# Pulsar_Buddy.net
KiCad netlist of a schematic drawn in EAGLE
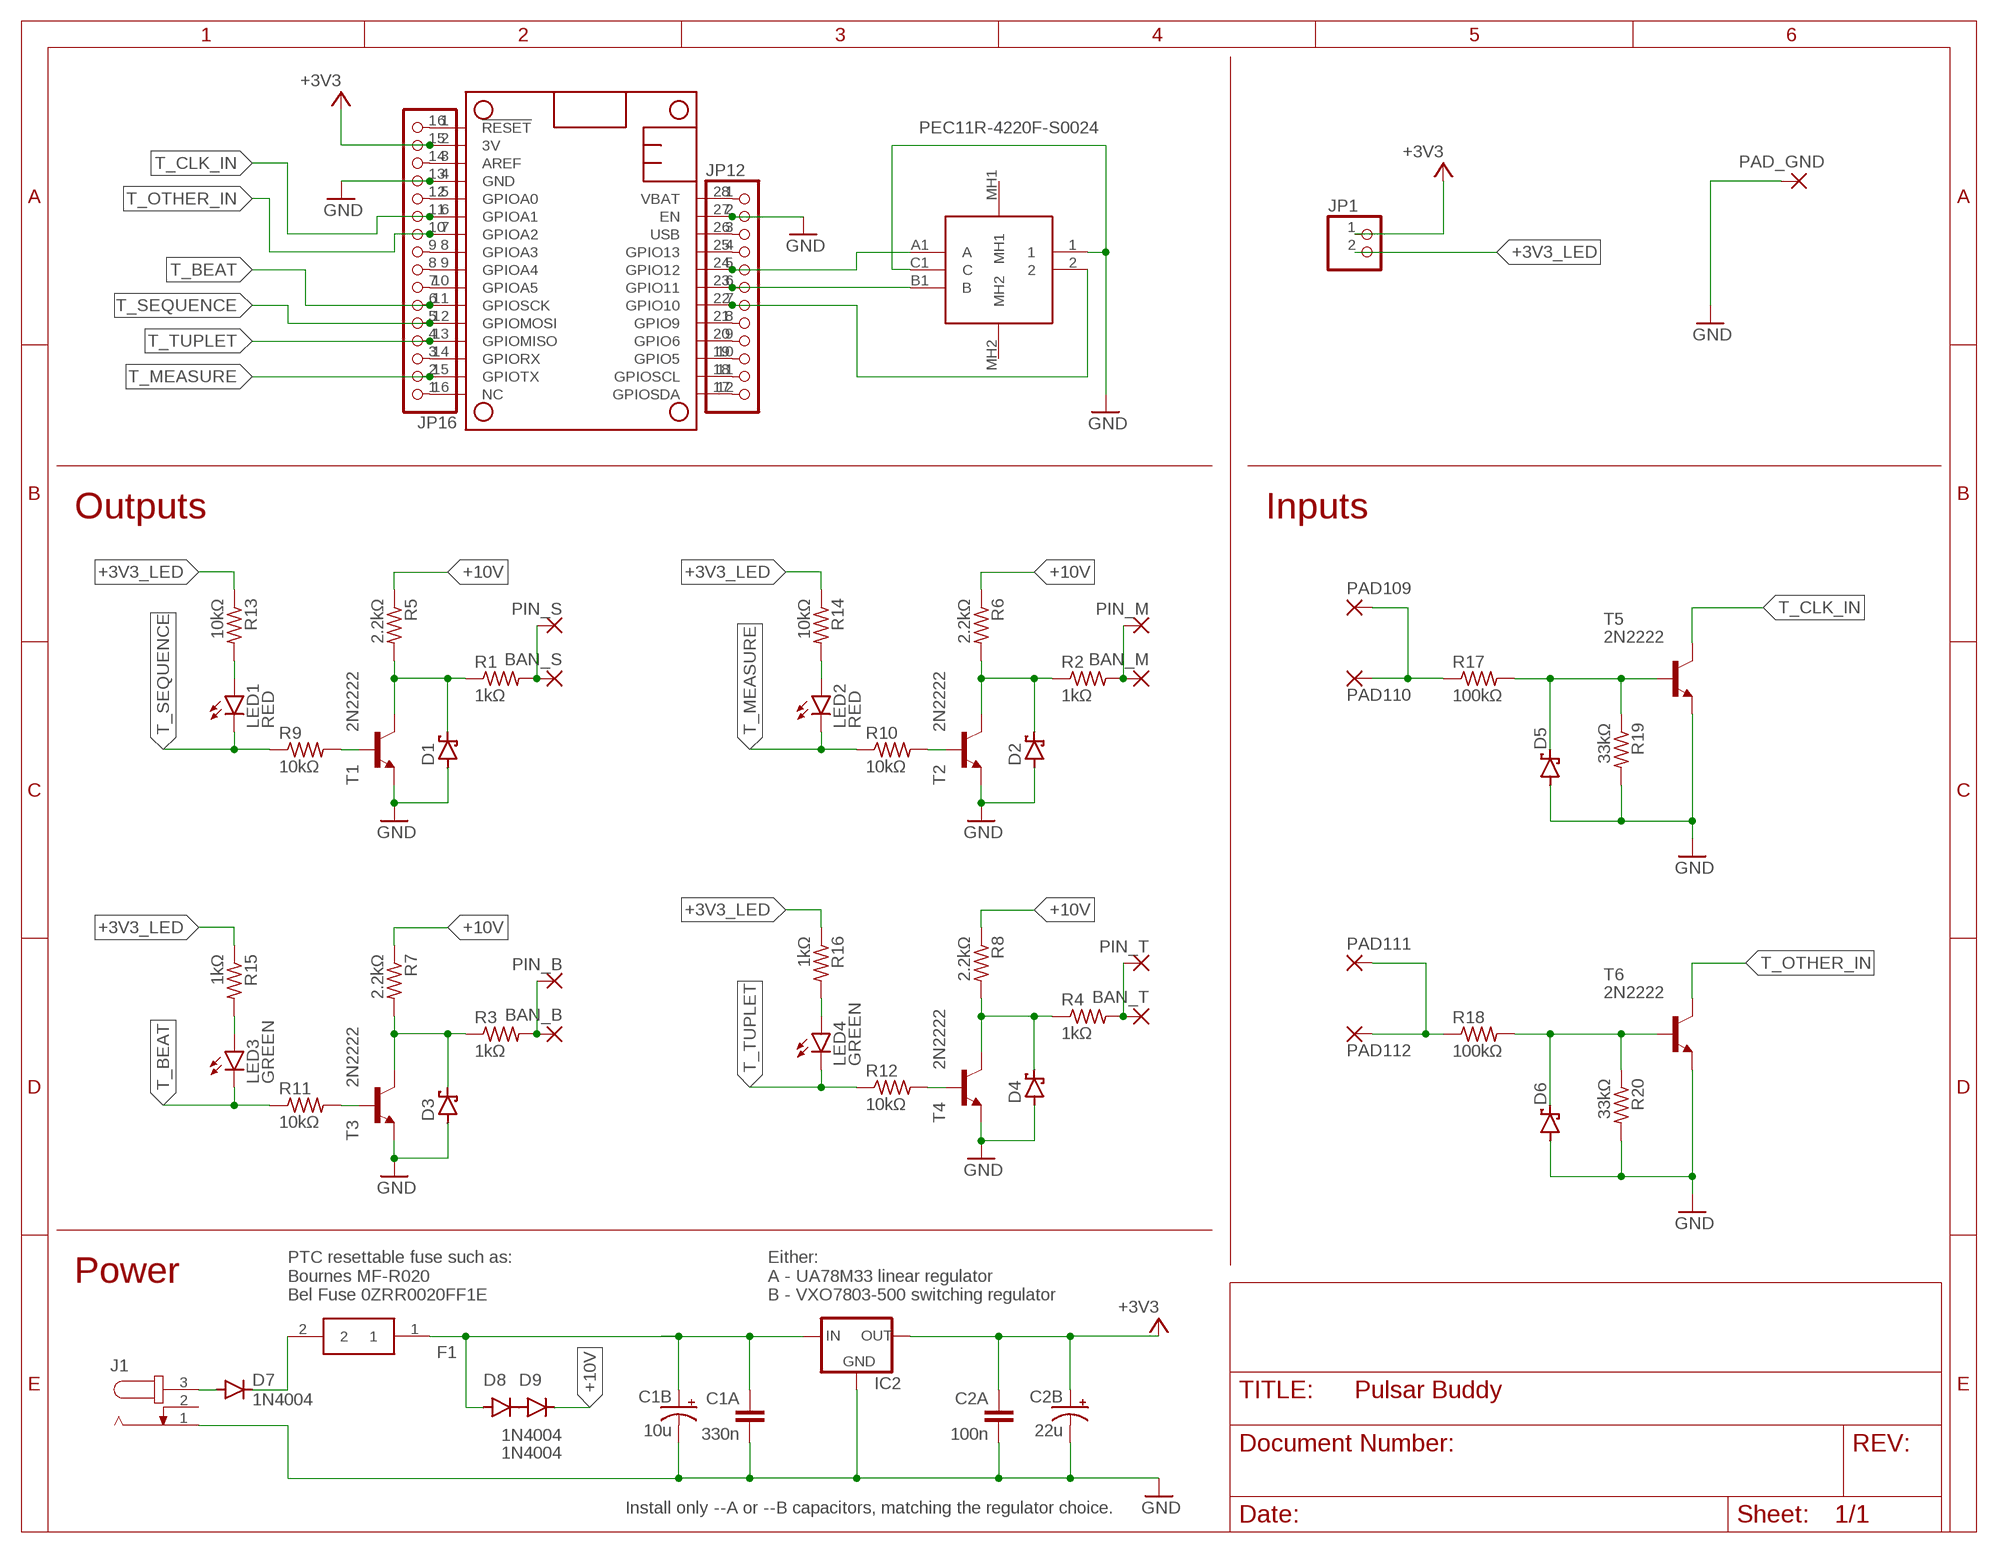
[diagram p0: schematic, sheet 1]

(export (version "E")
  (design (tool "Eeschema 10.0.6"))
  (components
    (comp (ref "BAN_B")
      (value "WIREPADBANANA")
      (footprint "eagle-import:BANANA")
      (libsource (lib "eagle-import") (part "WIREPADBANANA"))
    )
    (comp (ref "BAN_M")
      (value "WIREPADBANANA")
      (footprint "eagle-import:BANANA")
      (libsource (lib "eagle-import") (part "WIREPADBANANA"))
    )
    (comp (ref "BAN_S")
      (value "WIREPADBANANA")
      (footprint "eagle-import:BANANA")
      (libsource (lib "eagle-import") (part "WIREPADBANANA"))
    )
    (comp (ref "BAN_T")
      (value "WIREPADBANANA")
      (footprint "eagle-import:BANANA")
      (libsource (lib "eagle-import") (part "WIREPADBANANA"))
    )
    (comp (ref "C1A")
      (value "330n")
      (footprint "eagle-import:C025-024X044")
      (libsource (lib "eagle-import") (part "C-EU025-024X044"))
    )
    (comp (ref "C1B")
      (value "10u")
      (footprint "eagle-import:E5-5")
      (libsource (lib "eagle-import") (part "CPOL-USE5-5"))
    )
    (comp (ref "C2A")
      (value "100n")
      (footprint "eagle-import:C025-024X044")
      (libsource (lib "eagle-import") (part "C-EU025-024X044"))
    )
    (comp (ref "C2B")
      (value "22u")
      (footprint "eagle-import:E5-5")
      (libsource (lib "eagle-import") (part "CPOL-USE5-5"))
    )
    (comp (ref "D1")
      (value "SCHOTTKY-DIODEDO35-7")
      (footprint "eagle-import:DO35-7")
      (libsource (lib "eagle-import") (part "SCHOTTKY-DIODEDO35-7"))
    )
    (comp (ref "D2")
      (value "SCHOTTKY-DIODEDO35-7")
      (footprint "eagle-import:DO35-7")
      (libsource (lib "eagle-import") (part "SCHOTTKY-DIODEDO35-7"))
    )
    (comp (ref "D3")
      (value "SCHOTTKY-DIODEDO35-7")
      (footprint "eagle-import:DO35-7")
      (libsource (lib "eagle-import") (part "SCHOTTKY-DIODEDO35-7"))
    )
    (comp (ref "D4")
      (value "SCHOTTKY-DIODEDO35-7")
      (footprint "eagle-import:DO35-7")
      (libsource (lib "eagle-import") (part "SCHOTTKY-DIODEDO35-7"))
    )
    (comp (ref "D5")
      (value "SCHOTTKY-DIODEDO35-7")
      (footprint "eagle-import:DO35-7")
      (libsource (lib "eagle-import") (part "SCHOTTKY-DIODEDO35-7"))
    )
    (comp (ref "D6")
      (value "SCHOTTKY-DIODEDO35-7")
      (footprint "eagle-import:DO35-7")
      (libsource (lib "eagle-import") (part "SCHOTTKY-DIODEDO35-7"))
    )
    (comp (ref "D7")
      (value "1N4004")
      (footprint "eagle-import:DO41-10")
      (libsource (lib "eagle-import") (part "1N4004"))
    )
    (comp (ref "D8")
      (value "1N4004")
      (footprint "eagle-import:DO41-10")
      (libsource (lib "eagle-import") (part "1N4004"))
    )
    (comp (ref "D9")
      (value "1N4004")
      (footprint "eagle-import:DO41-10")
      (libsource (lib "eagle-import") (part "1N4004"))
    )
    (comp (ref "F1")
      (value "0ZRR0025FF1E")
      (footprint "eagle-import:0ZRR0025FF1E")
      (fields (field (name "MOUSER_PART_NUMBER") "530-0ZRR0025FF1E"))
      (libsource (lib "eagle-import") (part "0ZRR0025FF1E"))
    )
    (comp (ref "IC2")
      (value "UA78M33CKCSTO-220")
      (footprint "eagle-import:TO220H")
      (libsource (lib "eagle-import") (part "UA78M33CKCSTO-220"))
    )
    (comp (ref "J1")
      (value "JACK-PLUG0")
      (footprint "eagle-import:SPC4077")
      (libsource (lib "eagle-import") (part "JACK-PLUG0"))
    )
    (comp (ref "JP1")
      (value "PINHD-1X2")
      (footprint "eagle-import:1X02")
      (libsource (lib "eagle-import") (part "PINHD-1X2"))
    )
    (comp (ref "JP12")
      (value "HEADER-1X12")
      (footprint "eagle-import:1X12_ROUND")
      (libsource (lib "eagle-import") (part "HEADER-1X12"))
    )
    (comp (ref "JP16")
      (value "HEADER-1X16ROUND")
      (footprint "eagle-import:1X16_ROUND")
      (libsource (lib "eagle-import") (part "HEADER-1X16ROUND"))
    )
    (comp (ref "LED1")
      (value "RED")
      (footprint "eagle-import:LED5MM")
      (libsource (lib "eagle-import") (part "LED5MM"))
    )
    (comp (ref "LED2")
      (value "RED")
      (footprint "eagle-import:LED5MM")
      (libsource (lib "eagle-import") (part "LED5MM"))
    )
    (comp (ref "LED3")
      (value "GREEN")
      (footprint "eagle-import:LED5MM")
      (libsource (lib "eagle-import") (part "LED5MM"))
    )
    (comp (ref "LED4")
      (value "GREEN")
      (footprint "eagle-import:LED5MM")
      (libsource (lib "eagle-import") (part "LED5MM"))
    )
    (comp (ref "MS101")
      (value "FEATHERWING_NODIM")
      (footprint "eagle-import:FEATHERWING_DIM")
      (libsource (lib "eagle-import") (part "FEATHERWING_NODIM"))
    )
    (comp (ref "PAD109")
      (value "WIREPAD")
      (footprint "eagle-import:M3")
      (libsource (lib "eagle-import") (part "WIREPAD"))
    )
    (comp (ref "PAD110")
      (value "WIREPADBANANA")
      (footprint "eagle-import:BANANA")
      (libsource (lib "eagle-import") (part "WIREPADBANANA"))
    )
    (comp (ref "PAD111")
      (value "WIREPAD")
      (footprint "eagle-import:M3")
      (libsource (lib "eagle-import") (part "WIREPAD"))
    )
    (comp (ref "PAD112")
      (value "WIREPADBANANA")
      (footprint "eagle-import:BANANA")
      (libsource (lib "eagle-import") (part "WIREPADBANANA"))
    )
    (comp (ref "PAD_GND")
      (value "WIREPADBANANA-GND")
      (footprint "eagle-import:BANANA-GND")
      (libsource (lib "eagle-import") (part "WIREPADBANANA-GND"))
    )
    (comp (ref "PIN_B")
      (value "WIREPAD")
      (footprint "eagle-import:M3")
      (libsource (lib "eagle-import") (part "WIREPAD"))
    )
    (comp (ref "PIN_M")
      (value "WIREPAD")
      (footprint "eagle-import:M3")
      (libsource (lib "eagle-import") (part "WIREPAD"))
    )
    (comp (ref "PIN_S")
      (value "WIREPAD")
      (footprint "eagle-import:M3")
      (libsource (lib "eagle-import") (part "WIREPAD"))
    )
    (comp (ref "PIN_T")
      (value "WIREPAD")
      (footprint "eagle-import:M3")
      (libsource (lib "eagle-import") (part "WIREPAD"))
    )
    (comp (ref "R1")
      (value "1kΩ")
      (footprint "eagle-import:0204_7")
      (libsource (lib "eagle-import") (part "R-US_0204/7"))
    )
    (comp (ref "R2")
      (value "1kΩ")
      (footprint "eagle-import:0204_7")
      (libsource (lib "eagle-import") (part "R-US_0204/7"))
    )
    (comp (ref "R3")
      (value "1kΩ")
      (footprint "eagle-import:0204_7")
      (libsource (lib "eagle-import") (part "R-US_0204/7"))
    )
    (comp (ref "R4")
      (value "1kΩ")
      (footprint "eagle-import:0204_7")
      (libsource (lib "eagle-import") (part "R-US_0204/7"))
    )
    (comp (ref "R5")
      (value "2.2kΩ")
      (footprint "eagle-import:0204_7")
      (libsource (lib "eagle-import") (part "R-US_0204/7"))
    )
    (comp (ref "R6")
      (value "2.2kΩ")
      (footprint "eagle-import:0204_7")
      (libsource (lib "eagle-import") (part "R-US_0204/7"))
    )
    (comp (ref "R7")
      (value "2.2kΩ")
      (footprint "eagle-import:0204_7")
      (libsource (lib "eagle-import") (part "R-US_0204/7"))
    )
    (comp (ref "R8")
      (value "2.2kΩ")
      (footprint "eagle-import:0204_7")
      (libsource (lib "eagle-import") (part "R-US_0204/7"))
    )
    (comp (ref "R9")
      (value "10kΩ")
      (footprint "eagle-import:0204_7")
      (libsource (lib "eagle-import") (part "R-US_0204/7"))
    )
    (comp (ref "R10")
      (value "10kΩ")
      (footprint "eagle-import:0204_7")
      (libsource (lib "eagle-import") (part "R-US_0204/7"))
    )
    (comp (ref "R11")
      (value "10kΩ")
      (footprint "eagle-import:0204_7")
      (libsource (lib "eagle-import") (part "R-US_0204/7"))
    )
    (comp (ref "R12")
      (value "10kΩ")
      (footprint "eagle-import:0204_7")
      (libsource (lib "eagle-import") (part "R-US_0204/7"))
    )
    (comp (ref "R13")
      (value "10kΩ")
      (footprint "eagle-import:0204_7")
      (libsource (lib "eagle-import") (part "R-US_0204/7"))
    )
    (comp (ref "R14")
      (value "10kΩ")
      (footprint "eagle-import:0204_7")
      (libsource (lib "eagle-import") (part "R-US_0204/7"))
    )
    (comp (ref "R15")
      (value "1kΩ")
      (footprint "eagle-import:0204_7")
      (libsource (lib "eagle-import") (part "R-US_0204/7"))
    )
    (comp (ref "R16")
      (value "1kΩ")
      (footprint "eagle-import:0204_7")
      (libsource (lib "eagle-import") (part "R-US_0204/7"))
    )
    (comp (ref "R17")
      (value "100kΩ")
      (footprint "eagle-import:0204_7")
      (libsource (lib "eagle-import") (part "R-US_0204/7"))
    )
    (comp (ref "R18")
      (value "100kΩ")
      (footprint "eagle-import:0204_7")
      (libsource (lib "eagle-import") (part "R-US_0204/7"))
    )
    (comp (ref "R19")
      (value "33kΩ")
      (footprint "eagle-import:0204_7")
      (libsource (lib "eagle-import") (part "R-US_0204/7"))
    )
    (comp (ref "R20")
      (value "33kΩ")
      (footprint "eagle-import:0204_7")
      (libsource (lib "eagle-import") (part "R-US_0204/7"))
    )
    (comp (ref "SW1")
      (value "PEC11R-4220F-S0024")
      (footprint "eagle-import:PEC11R4220FS0024")
      (fields
        (field (name "MOUSER_PART_NUMBER") "652-PEC11R-4220F-S24")
        (field (name "RS_PART_NUMBER") "7377767P")
      )
      (libsource (lib "eagle-import") (part "PEC11R-4220F-S0024"))
    )
    (comp (ref "T1")
      (value "2N2222")
      (footprint "eagle-import:TO92-EBC-OVAL")
      (libsource (lib "eagle-import") (part "2N2222"))
    )
    (comp (ref "T2")
      (value "2N2222")
      (footprint "eagle-import:TO92-EBC-OVAL")
      (libsource (lib "eagle-import") (part "2N2222"))
    )
    (comp (ref "T3")
      (value "2N2222")
      (footprint "eagle-import:TO92-EBC-OVAL")
      (libsource (lib "eagle-import") (part "2N2222"))
    )
    (comp (ref "T4")
      (value "2N2222")
      (footprint "eagle-import:TO92-EBC-OVAL")
      (libsource (lib "eagle-import") (part "2N2222"))
    )
    (comp (ref "T5")
      (value "2N2222")
      (footprint "eagle-import:TO92-EBC-OVAL")
      (libsource (lib "eagle-import") (part "2N2222"))
    )
    (comp (ref "T6")
      (value "2N2222")
      (footprint "eagle-import:TO92-EBC-OVAL")
      (libsource (lib "eagle-import") (part "2N2222"))
    )
  )
  (nets
    (net (code "1") (name "+3V3") (class "Default")
      (node (ref "C2A") (pin "1") (pinfunction "1_1") (pintype "passive"))
      (node (ref "C2B") (pin "+") (pinfunction "+_+") (pintype "passive"))
      (node (ref "IC2") (pin "3") (pinfunction "OUT_3") (pintype "passive"))
      (node (ref "JP1") (pin "1") (pinfunction "1_1") (pintype "passive"))
      (node (ref "JP16") (pin "15") (pinfunction "15_15") (pintype "passive"))
      (node (ref "MS101") (pin "2") (pinfunction "3V_2") (pintype "power_in"))
    )
    (net (code "2") (name "+3V3_LED") (class "Default")
      (node (ref "JP1") (pin "2") (pinfunction "2_2") (pintype "passive"))
      (node (ref "R13") (pin "1") (pinfunction "1_1") (pintype "passive"))
      (node (ref "R14") (pin "1") (pinfunction "1_1") (pintype "passive"))
      (node (ref "R15") (pin "1") (pinfunction "1_1") (pintype "passive"))
      (node (ref "R16") (pin "1") (pinfunction "1_1") (pintype "passive"))
    )
    (net (code "3") (name "+10V") (class "Default")
      (node (ref "D9") (pin "C") (pinfunction "C_C") (pintype "passive"))
      (node (ref "R5") (pin "1") (pinfunction "1_1") (pintype "passive"))
      (node (ref "R6") (pin "1") (pinfunction "1_1") (pintype "passive"))
      (node (ref "R7") (pin "1") (pinfunction "1_1") (pintype "passive"))
      (node (ref "R8") (pin "1") (pinfunction "1_1") (pintype "passive"))
    )
    (net (code "4") (name "GND") (class "Default")
      (node (ref "C1A") (pin "2") (pinfunction "2_2") (pintype "passive"))
      (node (ref "C1B") (pin "-") (pinfunction "-_-") (pintype "passive"))
      (node (ref "C2A") (pin "2") (pinfunction "2_2") (pintype "passive"))
      (node (ref "C2B") (pin "-") (pinfunction "-_-") (pintype "passive"))
      (node (ref "D1") (pin "A") (pinfunction "A_A") (pintype "passive"))
      (node (ref "D2") (pin "A") (pinfunction "A_A") (pintype "passive"))
      (node (ref "D3") (pin "A") (pinfunction "A_A") (pintype "passive"))
      (node (ref "D4") (pin "A") (pinfunction "A_A") (pintype "passive"))
      (node (ref "D5") (pin "A") (pinfunction "A_A") (pintype "passive"))
      (node (ref "D6") (pin "A") (pinfunction "A_A") (pintype "passive"))
      (node (ref "IC2") (pin "2") (pinfunction "GND_2") (pintype "input"))
      (node (ref "J1") (pin "1") (pinfunction "1_1") (pintype "passive"))
      (node (ref "JP12") (pin "2") (pinfunction "2_2") (pintype "passive"))
      (node (ref "JP16") (pin "13") (pinfunction "13_13") (pintype "passive"))
      (node (ref "MS101") (pin "27") (pinfunction "EN_27") (pintype "passive"))
      (node (ref "MS101") (pin "4") (pinfunction "GND_4") (pintype "power_in"))
      (node (ref "PAD_GND") (pin "C") (pinfunction "P_C") (pintype "passive"))
      (node (ref "R19") (pin "2") (pinfunction "2_2") (pintype "passive"))
      (node (ref "R20") (pin "2") (pinfunction "2_2") (pintype "passive"))
      (node (ref "SW1") (pin "1") (pinfunction "1_1") (pintype "bidirectional"))
      (node (ref "SW1") (pin "C1") (pinfunction "C_C1") (pintype "bidirectional"))
      (node (ref "T1") (pin "E") (pinfunction "E_E") (pintype "passive"))
      (node (ref "T2") (pin "E") (pinfunction "E_E") (pintype "passive"))
      (node (ref "T3") (pin "E") (pinfunction "E_E") (pintype "passive"))
      (node (ref "T4") (pin "E") (pinfunction "E_E") (pintype "passive"))
      (node (ref "T5") (pin "E") (pinfunction "E_E") (pintype "passive"))
      (node (ref "T6") (pin "E") (pinfunction "E_E") (pintype "passive"))
    )
    (net (code "5") (name "Net-(BAN_B-P)") (class "Default")
      (node (ref "BAN_B") (pin "C") (pinfunction "P_C") (pintype "passive"))
      (node (ref "PIN_B") (pin "1") (pinfunction "P_1") (pintype "passive"))
      (node (ref "R3") (pin "2") (pinfunction "2_2") (pintype "passive"))
    )
    (net (code "6") (name "Net-(BAN_M-P)") (class "Default")
      (node (ref "BAN_M") (pin "C") (pinfunction "P_C") (pintype "passive"))
      (node (ref "PIN_M") (pin "1") (pinfunction "P_1") (pintype "passive"))
      (node (ref "R2") (pin "2") (pinfunction "2_2") (pintype "passive"))
    )
    (net (code "7") (name "Net-(BAN_S-P)") (class "Default")
      (node (ref "BAN_S") (pin "C") (pinfunction "P_C") (pintype "passive"))
      (node (ref "PIN_S") (pin "1") (pinfunction "P_1") (pintype "passive"))
      (node (ref "R1") (pin "2") (pinfunction "2_2") (pintype "passive"))
    )
    (net (code "8") (name "Net-(BAN_T-P)") (class "Default")
      (node (ref "BAN_T") (pin "C") (pinfunction "P_C") (pintype "passive"))
      (node (ref "PIN_T") (pin "1") (pinfunction "P_1") (pintype "passive"))
      (node (ref "R4") (pin "2") (pinfunction "2_2") (pintype "passive"))
    )
    (net (code "9") (name "Net-(D1-PadC)") (class "Default")
      (node (ref "D1") (pin "C") (pinfunction "C_C") (pintype "passive"))
      (node (ref "R1") (pin "1") (pinfunction "1_1") (pintype "passive"))
      (node (ref "R5") (pin "2") (pinfunction "2_2") (pintype "passive"))
      (node (ref "T1") (pin "C") (pinfunction "C_C") (pintype "passive"))
    )
    (net (code "10") (name "Net-(D2-PadC)") (class "Default")
      (node (ref "D2") (pin "C") (pinfunction "C_C") (pintype "passive"))
      (node (ref "R2") (pin "1") (pinfunction "1_1") (pintype "passive"))
      (node (ref "R6") (pin "2") (pinfunction "2_2") (pintype "passive"))
      (node (ref "T2") (pin "C") (pinfunction "C_C") (pintype "passive"))
    )
    (net (code "11") (name "Net-(D3-PadC)") (class "Default")
      (node (ref "D3") (pin "C") (pinfunction "C_C") (pintype "passive"))
      (node (ref "R3") (pin "1") (pinfunction "1_1") (pintype "passive"))
      (node (ref "R7") (pin "2") (pinfunction "2_2") (pintype "passive"))
      (node (ref "T3") (pin "C") (pinfunction "C_C") (pintype "passive"))
    )
    (net (code "12") (name "Net-(D4-PadC)") (class "Default")
      (node (ref "D4") (pin "C") (pinfunction "C_C") (pintype "passive"))
      (node (ref "R4") (pin "1") (pinfunction "1_1") (pintype "passive"))
      (node (ref "R8") (pin "2") (pinfunction "2_2") (pintype "passive"))
      (node (ref "T4") (pin "C") (pinfunction "C_C") (pintype "passive"))
    )
    (net (code "13") (name "Net-(D5-PadC)") (class "Default")
      (node (ref "D5") (pin "C") (pinfunction "C_C") (pintype "passive"))
      (node (ref "R17") (pin "2") (pinfunction "2_2") (pintype "passive"))
      (node (ref "R19") (pin "1") (pinfunction "1_1") (pintype "passive"))
      (node (ref "T5") (pin "B") (pinfunction "B_B") (pintype "passive"))
    )
    (net (code "14") (name "Net-(D6-PadC)") (class "Default")
      (node (ref "D6") (pin "C") (pinfunction "C_C") (pintype "passive"))
      (node (ref "R18") (pin "2") (pinfunction "2_2") (pintype "passive"))
      (node (ref "R20") (pin "1") (pinfunction "1_1") (pintype "passive"))
      (node (ref "T6") (pin "B") (pinfunction "B_B") (pintype "passive"))
    )
    (net (code "15") (name "Net-(D7-PadA)") (class "Default")
      (node (ref "D7") (pin "A") (pinfunction "A_A") (pintype "passive"))
      (node (ref "J1") (pin "3") (pinfunction "3_3") (pintype "passive"))
    )
    (net (code "16") (name "Net-(D7-PadC)") (class "Default")
      (node (ref "D7") (pin "C") (pinfunction "C_C") (pintype "passive"))
      (node (ref "F1") (pin "2") (pinfunction "2_2") (pintype "bidirectional"))
    )
    (net (code "17") (name "Net-(D8-PadC)") (class "Default")
      (node (ref "D8") (pin "C") (pinfunction "C_C") (pintype "passive"))
      (node (ref "D9") (pin "A") (pinfunction "A_A") (pintype "passive"))
    )
    (net (code "18") (name "Net-(IC2-IN)") (class "Default")
      (node (ref "C1A") (pin "1") (pinfunction "1_1") (pintype "passive"))
      (node (ref "C1B") (pin "+") (pinfunction "+_+") (pintype "passive"))
      (node (ref "D8") (pin "A") (pinfunction "A_A") (pintype "passive"))
      (node (ref "F1") (pin "1") (pinfunction "1_1") (pintype "bidirectional"))
      (node (ref "IC2") (pin "1") (pinfunction "IN_1") (pintype "input"))
    )
    (net (code "19") (name "Net-(LED1-PadA)") (class "Default")
      (node (ref "LED1") (pin "A") (pinfunction "A_A") (pintype "passive"))
      (node (ref "R13") (pin "2") (pinfunction "2_2") (pintype "passive"))
    )
    (net (code "20") (name "Net-(LED2-PadA)") (class "Default")
      (node (ref "LED2") (pin "A") (pinfunction "A_A") (pintype "passive"))
      (node (ref "R14") (pin "2") (pinfunction "2_2") (pintype "passive"))
    )
    (net (code "21") (name "Net-(LED3-PadA)") (class "Default")
      (node (ref "LED3") (pin "A") (pinfunction "A_A") (pintype "passive"))
      (node (ref "R15") (pin "2") (pinfunction "2_2") (pintype "passive"))
    )
    (net (code "22") (name "Net-(LED4-PadA)") (class "Default")
      (node (ref "LED4") (pin "A") (pinfunction "A_A") (pintype "passive"))
      (node (ref "R16") (pin "2") (pinfunction "2_2") (pintype "passive"))
    )
    (net (code "23") (name "Net-(MS101-AREF)") (class "Default")
      (node (ref "JP16") (pin "14") (pinfunction "14_14") (pintype "passive"))
      (node (ref "MS101") (pin "3") (pinfunction "AREF_3") (pintype "passive"))
    )
    (net (code "24") (name "Net-(MS101-GPIO5)") (class "Default")
      (node (ref "JP12") (pin "10") (pinfunction "10_10") (pintype "passive"))
      (node (ref "MS101") (pin "19") (pinfunction "GPIO5_19") (pintype "bidirectional"))
    )
    (net (code "25") (name "Net-(MS101-GPIO6)") (class "Default")
      (node (ref "JP12") (pin "9") (pinfunction "9_9") (pintype "passive"))
      (node (ref "MS101") (pin "20") (pinfunction "GPIO6_20") (pintype "bidirectional"))
    )
    (net (code "26") (name "Net-(MS101-GPIO9)") (class "Default")
      (node (ref "JP12") (pin "8") (pinfunction "8_8") (pintype "passive"))
      (node (ref "MS101") (pin "21") (pinfunction "GPIO9_21") (pintype "bidirectional"))
    )
    (net (code "27") (name "Net-(MS101-GPIO10)") (class "Default")
      (node (ref "JP12") (pin "7") (pinfunction "7_7") (pintype "passive"))
      (node (ref "MS101") (pin "22") (pinfunction "GPIO10_22") (pintype "bidirectional"))
      (node (ref "SW1") (pin "2") (pinfunction "2_2") (pintype "bidirectional"))
    )
    (net (code "28") (name "Net-(MS101-GPIO11)") (class "Default")
      (node (ref "JP12") (pin "6") (pinfunction "6_6") (pintype "passive"))
      (node (ref "MS101") (pin "23") (pinfunction "GPIO11_23") (pintype "bidirectional"))
      (node (ref "SW1") (pin "B1") (pinfunction "B_B1") (pintype "bidirectional"))
    )
    (net (code "29") (name "Net-(MS101-GPIO12)") (class "Default")
      (node (ref "JP12") (pin "5") (pinfunction "5_5") (pintype "passive"))
      (node (ref "MS101") (pin "24") (pinfunction "GPIO12_24") (pintype "bidirectional"))
      (node (ref "SW1") (pin "A1") (pinfunction "A_A1") (pintype "bidirectional"))
    )
    (net (code "30") (name "Net-(MS101-GPIO13)") (class "Default")
      (node (ref "JP12") (pin "4") (pinfunction "4_4") (pintype "passive"))
      (node (ref "MS101") (pin "25") (pinfunction "GPIO13_25") (pintype "bidirectional"))
    )
    (net (code "31") (name "Net-(MS101-GPIOA0)") (class "Default")
      (node (ref "JP16") (pin "12") (pinfunction "12_12") (pintype "passive"))
      (node (ref "MS101") (pin "5") (pinfunction "GPIOA0_5") (pintype "bidirectional"))
    )
    (net (code "32") (name "Net-(MS101-GPIOA3)") (class "Default")
      (node (ref "JP16") (pin "9") (pinfunction "9_9") (pintype "passive"))
      (node (ref "MS101") (pin "8") (pinfunction "GPIOA3_8") (pintype "bidirectional"))
    )
    (net (code "33") (name "Net-(MS101-GPIOA4)") (class "Default")
      (node (ref "JP16") (pin "8") (pinfunction "8_8") (pintype "passive"))
      (node (ref "MS101") (pin "9") (pinfunction "GPIOA4_9") (pintype "bidirectional"))
    )
    (net (code "34") (name "Net-(MS101-GPIOA5)") (class "Default")
      (node (ref "JP16") (pin "7") (pinfunction "7_7") (pintype "passive"))
      (node (ref "MS101") (pin "10") (pinfunction "GPIOA5_10") (pintype "bidirectional"))
    )
    (net (code "35") (name "Net-(MS101-GPIORX)") (class "Default")
      (node (ref "JP16") (pin "3") (pinfunction "3_3") (pintype "passive"))
      (node (ref "MS101") (pin "14") (pinfunction "GPIORX_14") (pintype "bidirectional"))
    )
    (net (code "36") (name "Net-(MS101-GPIOSCL)") (class "Default")
      (node (ref "JP12") (pin "11") (pinfunction "11_11") (pintype "passive"))
      (node (ref "MS101") (pin "18") (pinfunction "GPIOSCL_18") (pintype "bidirectional"))
    )
    (net (code "37") (name "Net-(MS101-GPIOSDA)") (class "Default")
      (node (ref "JP12") (pin "12") (pinfunction "12_12") (pintype "passive"))
      (node (ref "MS101") (pin "17") (pinfunction "GPIOSDA_17") (pintype "bidirectional"))
    )
    (net (code "38") (name "Net-(MS101-NC)") (class "Default")
      (node (ref "JP16") (pin "1") (pinfunction "1_1") (pintype "passive"))
      (node (ref "MS101") (pin "16") (pinfunction "NC_16") (pintype "passive"))
    )
    (net (code "39") (name "Net-(MS101-USB)") (class "Default")
      (node (ref "JP12") (pin "3") (pinfunction "3_3") (pintype "passive"))
      (node (ref "MS101") (pin "26") (pinfunction "USB_26") (pintype "power_in"))
    )
    (net (code "40") (name "Net-(MS101-VBAT)") (class "Default")
      (node (ref "JP12") (pin "1") (pinfunction "1_1") (pintype "passive"))
      (node (ref "MS101") (pin "28") (pinfunction "VBAT_28") (pintype "power_in"))
    )
    (net (code "41") (name "Net-(MS101-~{RESET})") (class "Default")
      (node (ref "JP16") (pin "16") (pinfunction "16_16") (pintype "passive"))
      (node (ref "MS101") (pin "1") (pinfunction "~{RESET}_1") (pintype "input"))
    )
    (net (code "42") (name "Net-(PAD109-P)") (class "Default")
      (node (ref "PAD109") (pin "1") (pinfunction "P_1") (pintype "passive"))
      (node (ref "PAD110") (pin "C") (pinfunction "P_C") (pintype "passive"))
      (node (ref "R17") (pin "1") (pinfunction "1_1") (pintype "passive"))
    )
    (net (code "43") (name "Net-(PAD111-P)") (class "Default")
      (node (ref "PAD111") (pin "1") (pinfunction "P_1") (pintype "passive"))
      (node (ref "PAD112") (pin "C") (pinfunction "P_C") (pintype "passive"))
      (node (ref "R18") (pin "1") (pinfunction "1_1") (pintype "passive"))
    )
    (net (code "44") (name "Net-(R9-Pad2)") (class "Default")
      (node (ref "R9") (pin "2") (pinfunction "2_2") (pintype "passive"))
      (node (ref "T1") (pin "B") (pinfunction "B_B") (pintype "passive"))
    )
    (net (code "45") (name "Net-(R10-Pad2)") (class "Default")
      (node (ref "R10") (pin "2") (pinfunction "2_2") (pintype "passive"))
      (node (ref "T2") (pin "B") (pinfunction "B_B") (pintype "passive"))
    )
    (net (code "46") (name "Net-(R11-Pad2)") (class "Default")
      (node (ref "R11") (pin "2") (pinfunction "2_2") (pintype "passive"))
      (node (ref "T3") (pin "B") (pinfunction "B_B") (pintype "passive"))
    )
    (net (code "47") (name "Net-(R12-Pad2)") (class "Default")
      (node (ref "R12") (pin "2") (pinfunction "2_2") (pintype "passive"))
      (node (ref "T4") (pin "B") (pinfunction "B_B") (pintype "passive"))
    )
    (net (code "48") (name "T_BEAT") (class "Default")
      (node (ref "JP16") (pin "6") (pinfunction "6_6") (pintype "passive"))
      (node (ref "LED3") (pin "K") (pinfunction "C_K") (pintype "passive"))
      (node (ref "MS101") (pin "11") (pinfunction "GPIOSCK_11") (pintype "bidirectional"))
      (node (ref "R11") (pin "1") (pinfunction "1_1") (pintype "passive"))
    )
    (net (code "49") (name "T_CLK_IN") (class "Default")
      (node (ref "JP16") (pin "11") (pinfunction "11_11") (pintype "passive"))
      (node (ref "MS101") (pin "6") (pinfunction "GPIOA1_6") (pintype "bidirectional"))
      (node (ref "T5") (pin "C") (pinfunction "C_C") (pintype "passive"))
    )
    (net (code "50") (name "T_MEASURE") (class "Default")
      (node (ref "JP16") (pin "2") (pinfunction "2_2") (pintype "passive"))
      (node (ref "LED2") (pin "K") (pinfunction "C_K") (pintype "passive"))
      (node (ref "MS101") (pin "15") (pinfunction "GPIOTX_15") (pintype "bidirectional"))
      (node (ref "R10") (pin "1") (pinfunction "1_1") (pintype "passive"))
    )
    (net (code "51") (name "T_OTHER_IN") (class "Default")
      (node (ref "JP16") (pin "10") (pinfunction "10_10") (pintype "passive"))
      (node (ref "MS101") (pin "7") (pinfunction "GPIOA2_7") (pintype "bidirectional"))
      (node (ref "T6") (pin "C") (pinfunction "C_C") (pintype "passive"))
    )
    (net (code "52") (name "T_SEQUENCE") (class "Default")
      (node (ref "JP16") (pin "5") (pinfunction "5_5") (pintype "passive"))
      (node (ref "LED1") (pin "K") (pinfunction "C_K") (pintype "passive"))
      (node (ref "MS101") (pin "12") (pinfunction "GPIOMOSI_12") (pintype "bidirectional"))
      (node (ref "R9") (pin "1") (pinfunction "1_1") (pintype "passive"))
    )
    (net (code "53") (name "T_TUPLET") (class "Default")
      (node (ref "JP16") (pin "4") (pinfunction "4_4") (pintype "passive"))
      (node (ref "LED4") (pin "K") (pinfunction "C_K") (pintype "passive"))
      (node (ref "MS101") (pin "13") (pinfunction "GPIOMISO_13") (pintype "bidirectional"))
      (node (ref "R12") (pin "1") (pinfunction "1_1") (pintype "passive"))
    )
    (net (code "54") (name "unconnected-(J1-Pad2)") (class "Default")
      (node (ref "J1") (pin "2") (pinfunction "2_2") (pintype "passive"))
    )
    (net (code "55") (name "unconnected-(SW1-PadMH1)") (class "Default")
      (node (ref "SW1") (pin "MH1") (pinfunction "MH1_MH1") (pintype "bidirectional"))
    )
    (net (code "56") (name "unconnected-(SW1-PadMH2)") (class "Default")
      (node (ref "SW1") (pin "MH2") (pinfunction "MH2_MH2") (pintype "bidirectional"))
    )
  )
)
